# Electrode-Front-End-Digital.net
KiCad netlist of a schematic drawn in Altium Designer
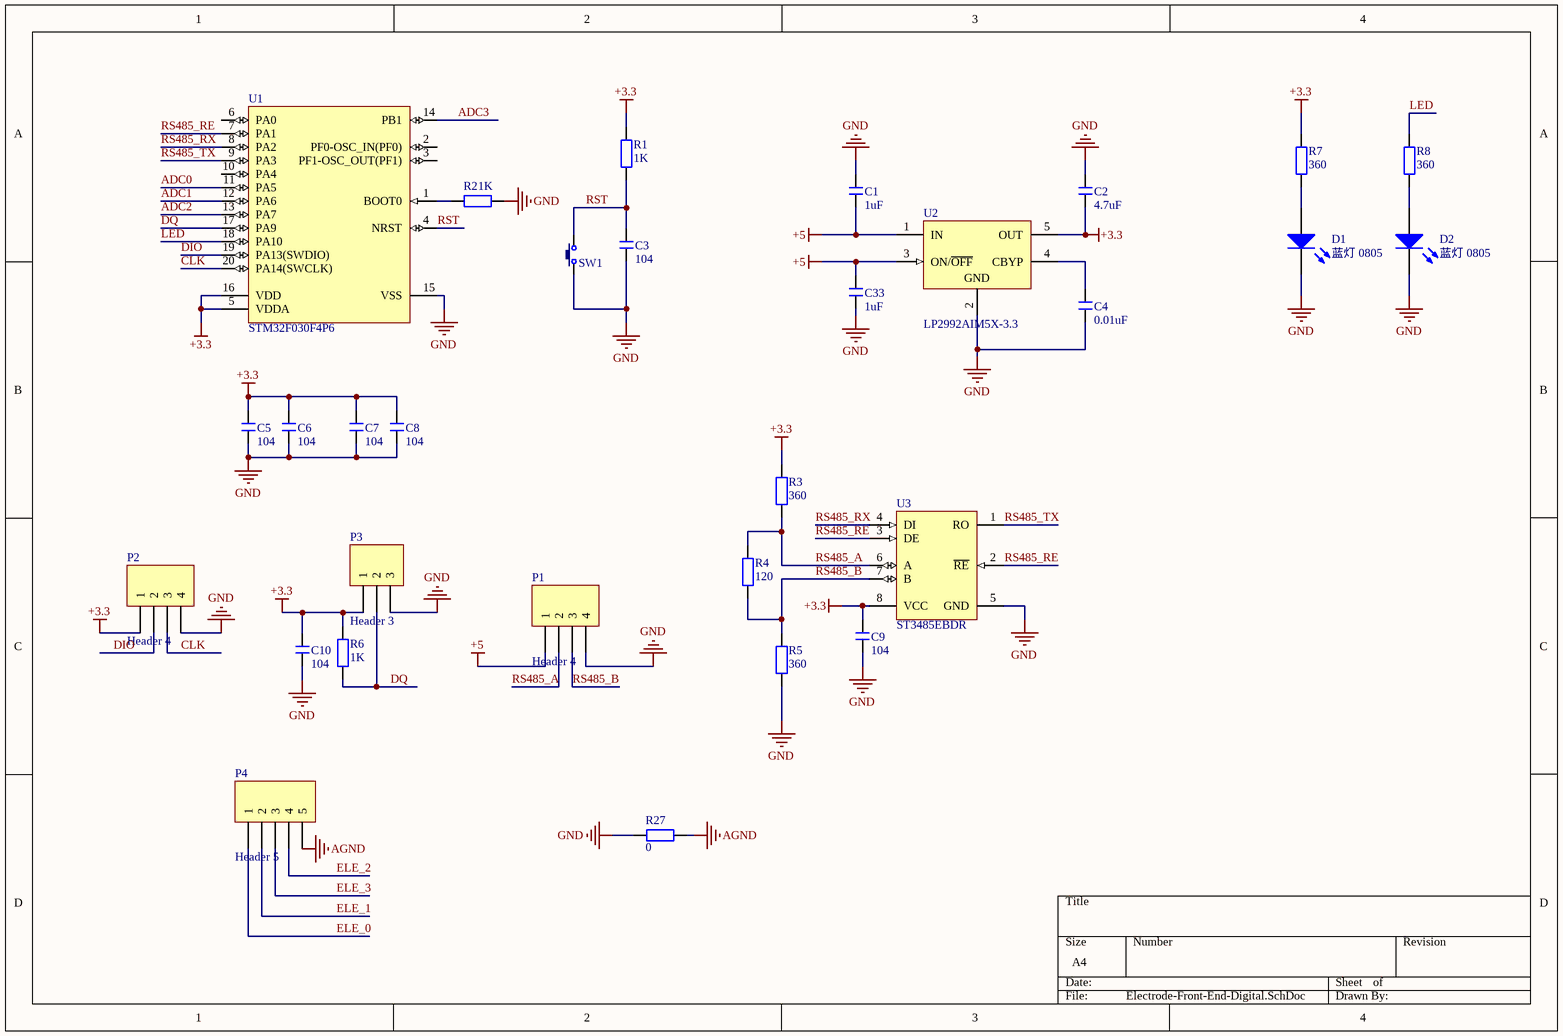
[diagram p0: Electrode-Front-End-Digital.SchDoc]

(export (version "E")
  (design (tool "Eeschema 10.0.6"))
  (components
    (comp (ref "C1")
      (value "1uF")
      (footprint "C 0603_L")
      (description "无极性贴片电容")
      (libsource (lib "电容-电阻-电感-电位器") (part "C"))
    )
    (comp (ref "C2")
      (value "4.7uF")
      (footprint "C 0603_L")
      (description "无极性贴片电容")
      (libsource (lib "电容-电阻-电感-电位器") (part "C"))
    )
    (comp (ref "C3")
      (value "104")
      (footprint "C 0603_L")
      (description "无极性贴片电容")
      (libsource (lib "电容-电阻-电感-电位器") (part "C"))
    )
    (comp (ref "C4")
      (value "0.01uF")
      (footprint "C 0603_L")
      (description "无极性贴片电容")
      (libsource (lib "电容-电阻-电感-电位器") (part "C"))
    )
    (comp (ref "C5")
      (value "104")
      (footprint "C 0603_L")
      (description "无极性贴片电容")
      (libsource (lib "电容-电阻-电感-电位器") (part "C"))
    )
    (comp (ref "C6")
      (value "104")
      (footprint "C 0603_L")
      (description "无极性贴片电容")
      (libsource (lib "电容-电阻-电感-电位器") (part "C"))
    )
    (comp (ref "C7")
      (value "104")
      (footprint "C 0603_L")
      (description "无极性贴片电容")
      (libsource (lib "电容-电阻-电感-电位器") (part "C"))
    )
    (comp (ref "C8")
      (value "104")
      (footprint "C 0603_L")
      (description "无极性贴片电容")
      (libsource (lib "电容-电阻-电感-电位器") (part "C"))
    )
    (comp (ref "C9")
      (value "104")
      (footprint "C 0603_L")
      (description "无极性贴片电容")
      (libsource (lib "电容-电阻-电感-电位器") (part "C"))
    )
    (comp (ref "C10")
      (value "104")
      (footprint "C 0603_L")
      (description "无极性贴片电容")
      (libsource (lib "电容-电阻-电感-电位器") (part "C"))
    )
    (comp (ref "C33")
      (value "1uF")
      (footprint "C 0603_L")
      (description "无极性贴片电容")
      (libsource (lib "电容-电阻-电感-电位器") (part "C"))
    )
    (comp (ref "D1")
      (value "蓝灯 0805")
      (footprint "0805_LED_S1")
      (description "发光二极管")
      (libsource (lib "JLC") (part "0805 蓝灯"))
    )
    (comp (ref "D2")
      (value "蓝灯 0805")
      (footprint "0805_LED_S1")
      (description "发光二极管")
      (libsource (lib "JLC") (part "0805 蓝灯"))
    )
    (comp (ref "P1")
      (value "Header 4")
      (footprint "HDR1X4")
      (description "Header, 4-Pin")
      (fields (field (name "PUBLISHER") "Altium Limited"))
      (libsource (lib "Miscellaneous Connectors") (part "Header 4"))
    )
    (comp (ref "P2")
      (value "Header 4")
      (footprint "HDR1X4")
      (description "Header, 4-Pin")
      (fields (field (name "PUBLISHER") "Altium Limited"))
      (libsource (lib "Miscellaneous Connectors") (part "Header 4"))
    )
    (comp (ref "P3")
      (value "Header 3")
      (footprint "HDR1X3")
      (description "Header, 3-Pin")
      (fields (field (name "PUBLISHER") "Altium Limited"))
      (libsource (lib "Miscellaneous Connectors") (part "Header 3"))
    )
    (comp (ref "P4")
      (value "Header 5")
      (footprint "HDR1X5")
      (description "Header, 5-Pin")
      (fields (field (name "PUBLISHER") "Altium Limited"))
      (libsource (lib "Miscellaneous Connectors") (part "Header 5"))
    )
    (comp (ref "R1")
      (value "1K")
      (footprint "R 0603_L")
      (description "贴片电阻")
      (libsource (lib "电容-电阻-电感-电位器") (part "R"))
    )
    (comp (ref "R2")
      (value "1K")
      (footprint "R 0603_L")
      (description "贴片电阻")
      (libsource (lib "电容-电阻-电感-电位器") (part "R"))
    )
    (comp (ref "R3")
      (value "360")
      (footprint "R 0603_L")
      (description "贴片电阻")
      (libsource (lib "电容-电阻-电感-电位器") (part "R"))
    )
    (comp (ref "R4")
      (value "120")
      (footprint "R 0603_L")
      (description "贴片电阻")
      (libsource (lib "电容-电阻-电感-电位器") (part "R"))
    )
    (comp (ref "R5")
      (value "360")
      (footprint "R 0603_L")
      (description "贴片电阻")
      (libsource (lib "电容-电阻-电感-电位器") (part "R"))
    )
    (comp (ref "R6")
      (value "1K")
      (footprint "R 0603_L")
      (description "贴片电阻")
      (libsource (lib "电容-电阻-电感-电位器") (part "R"))
    )
    (comp (ref "R7")
      (value "360")
      (footprint "R 0603_L")
      (description "贴片电阻")
      (libsource (lib "电容-电阻-电感-电位器") (part "R"))
    )
    (comp (ref "R8")
      (value "360")
      (footprint "R 0603_L")
      (description "贴片电阻")
      (libsource (lib "电容-电阻-电感-电位器") (part "R"))
    )
    (comp (ref "R27")
      (value "0")
      (footprint "R 0603_L")
      (description "贴片电阻")
      (libsource (lib "电容-电阻-电感-电位器") (part "R"))
    )
    (comp (ref "SW1")
      (value "3x6x5")
      (footprint "TSW SMD-3*6*2.5")
      (description "3x6轻触开关")
      (libsource (lib "按键-开关") (part "TSW 3x6"))
    )
    (comp (ref "U1")
      (value "STM32F030F4P6")
      (footprint "STM-TSSOP20_L")
      (libsource (lib "Altium Content Vault") (part "MC-ARM-STM32F030-IL20"))
    )
    (comp (ref "U2")
      (value "LP2992AIM5X-3.3")
      (footprint "MF05A_N")
      (description "Micropower 250 mA Low-Noise Ultra Low-Dropout Regulator, 5-pin SOT-23")
      (fields (field (name "MANUFACTURER") "National Semiconductor"))
      (libsource (lib "Altium Content Vault") (part "PM-REG-LP2985-SOT5"))
    )
    (comp (ref "U3")
      (value "ST3485EBDR")
      (footprint "STM-SO-8_C_L")
      (fields (field (name "MANUFACTURER") "STMicroelectronics"))
      (libsource (lib "Altium Content Vault") (part "STM-ST3485EBDR-SO-8"))
    )
  )
  (nets
    (net (code "1") (name "+3.3") (class "Default")
      (node (ref "C10") (pin "2") (pinfunction "2_2") (pintype "passive"))
      (node (ref "C2") (pin "1") (pinfunction "1_1") (pintype "passive"))
      (node (ref "C5") (pin "2") (pinfunction "2_2") (pintype "passive"))
      (node (ref "C6") (pin "2") (pinfunction "2_2") (pintype "passive"))
      (node (ref "C7") (pin "2") (pinfunction "2_2") (pintype "passive"))
      (node (ref "C8") (pin "2") (pinfunction "2_2") (pintype "passive"))
      (node (ref "C9") (pin "2") (pinfunction "2_2") (pintype "passive"))
      (node (ref "P2") (pin "1") (pinfunction "1_1") (pintype "passive"))
      (node (ref "P3") (pin "1") (pinfunction "1_1") (pintype "passive"))
      (node (ref "R1") (pin "2") (pinfunction "2_2") (pintype "passive"))
      (node (ref "R3") (pin "2") (pinfunction "2_2") (pintype "passive"))
      (node (ref "R6") (pin "2") (pinfunction "2_2") (pintype "passive"))
      (node (ref "R7") (pin "2") (pinfunction "2_2") (pintype "passive"))
      (node (ref "U1") (pin "16") (pinfunction "VDD_16") (pintype "power_in"))
      (node (ref "U1") (pin "5") (pinfunction "VDDA_5") (pintype "power_in"))
      (node (ref "U2") (pin "5") (pinfunction "OUT_5") (pintype "power_in"))
      (node (ref "U3") (pin "8") (pinfunction "VCC_8") (pintype "power_in"))
    )
    (net (code "2") (name "+5") (class "Default")
      (node (ref "C1") (pin "1") (pinfunction "1_1") (pintype "passive"))
      (node (ref "C33") (pin "2") (pinfunction "2_2") (pintype "passive"))
      (node (ref "P1") (pin "1") (pinfunction "1_1") (pintype "passive"))
      (node (ref "U2") (pin "1") (pinfunction "IN_1") (pintype "power_in"))
      (node (ref "U2") (pin "3") (pinfunction "ON/~{OFF}_3") (pintype "input"))
    )
    (net (code "3") (name "/ADC0") (class "Default")
      (node (ref "U1") (pin "11") (pinfunction "PA5_11") (pintype "bidirectional"))
    )
    (net (code "4") (name "/ADC1") (class "Default")
      (node (ref "U1") (pin "12") (pinfunction "PA6_12") (pintype "bidirectional"))
    )
    (net (code "5") (name "/ADC2") (class "Default")
      (node (ref "U1") (pin "13") (pinfunction "PA7_13") (pintype "bidirectional"))
    )
    (net (code "6") (name "/ADC3") (class "Default")
      (node (ref "U1") (pin "14") (pinfunction "PB1_14") (pintype "bidirectional"))
    )
    (net (code "7") (name "/CLK") (class "Default")
      (node (ref "P2") (pin "3") (pinfunction "3_3") (pintype "passive"))
      (node (ref "U1") (pin "20") (pinfunction "PA14(SWCLK)_20") (pintype "bidirectional"))
    )
    (net (code "8") (name "/DIO") (class "Default")
      (node (ref "P2") (pin "2") (pinfunction "2_2") (pintype "passive"))
      (node (ref "U1") (pin "19") (pinfunction "PA13(SWDIO)_19") (pintype "bidirectional"))
    )
    (net (code "9") (name "/DQ") (class "Default")
      (node (ref "P3") (pin "2") (pinfunction "2_2") (pintype "passive"))
      (node (ref "R6") (pin "1") (pinfunction "1_1") (pintype "passive"))
      (node (ref "U1") (pin "17") (pinfunction "PA9_17") (pintype "bidirectional"))
    )
    (net (code "10") (name "/ELE_0") (class "Default")
      (node (ref "P4") (pin "1") (pinfunction "1_1") (pintype "passive"))
    )
    (net (code "11") (name "/ELE_1") (class "Default")
      (node (ref "P4") (pin "2") (pinfunction "2_2") (pintype "passive"))
    )
    (net (code "12") (name "/ELE_2") (class "Default")
      (node (ref "P4") (pin "4") (pinfunction "4_4") (pintype "passive"))
    )
    (net (code "13") (name "/ELE_3") (class "Default")
      (node (ref "P4") (pin "3") (pinfunction "3_3") (pintype "passive"))
    )
    (net (code "14") (name "/LED") (class "Default")
      (node (ref "R8") (pin "2") (pinfunction "2_2") (pintype "passive"))
      (node (ref "U1") (pin "18") (pinfunction "PA10_18") (pintype "bidirectional"))
    )
    (net (code "15") (name "/RS485_A") (class "Default")
      (node (ref "P1") (pin "2") (pinfunction "2_2") (pintype "passive"))
      (node (ref "R3") (pin "1") (pinfunction "1_1") (pintype "passive"))
      (node (ref "R4") (pin "2") (pinfunction "2_2") (pintype "passive"))
      (node (ref "U3") (pin "6") (pinfunction "A_6") (pintype "bidirectional"))
    )
    (net (code "16") (name "/RS485_B") (class "Default")
      (node (ref "P1") (pin "3") (pinfunction "3_3") (pintype "passive"))
      (node (ref "R4") (pin "1") (pinfunction "1_1") (pintype "passive"))
      (node (ref "R5") (pin "2") (pinfunction "2_2") (pintype "passive"))
      (node (ref "U3") (pin "7") (pinfunction "B_7") (pintype "bidirectional"))
    )
    (net (code "17") (name "/RS485_RE") (class "Default")
      (node (ref "U1") (pin "7") (pinfunction "PA1_7") (pintype "bidirectional"))
      (node (ref "U3") (pin "2") (pinfunction "~{RE}_2") (pintype "input"))
      (node (ref "U3") (pin "3") (pinfunction "DE_3") (pintype "input"))
    )
    (net (code "18") (name "/RS485_RX") (class "Default")
      (node (ref "U1") (pin "8") (pinfunction "PA2_8") (pintype "bidirectional"))
      (node (ref "U3") (pin "4") (pinfunction "DI_4") (pintype "input"))
    )
    (net (code "19") (name "/RS485_TX") (class "Default")
      (node (ref "U1") (pin "9") (pinfunction "PA3_9") (pintype "bidirectional"))
      (node (ref "U3") (pin "1") (pinfunction "RO_1") (pintype "tri_state"))
    )
    (net (code "20") (name "/RST") (class "Default")
      (node (ref "C3") (pin "2") (pinfunction "2_2") (pintype "passive"))
      (node (ref "R1") (pin "1") (pinfunction "1_1") (pintype "passive"))
      (node (ref "SW1") (pin "2") (pinfunction "2_2") (pintype "passive"))
      (node (ref "U1") (pin "4") (pinfunction "NRST_4") (pintype "bidirectional"))
    )
    (net (code "21") (name "AGND") (class "Default")
      (node (ref "P4") (pin "5") (pinfunction "5_5") (pintype "passive"))
      (node (ref "R27") (pin "2") (pinfunction "2_2") (pintype "passive"))
    )
    (net (code "22") (name "GND") (class "Default")
      (node (ref "C1") (pin "2") (pinfunction "2_2") (pintype "passive"))
      (node (ref "C10") (pin "1") (pinfunction "1_1") (pintype "passive"))
      (node (ref "C2") (pin "2") (pinfunction "2_2") (pintype "passive"))
      (node (ref "C3") (pin "1") (pinfunction "1_1") (pintype "passive"))
      (node (ref "C33") (pin "1") (pinfunction "1_1") (pintype "passive"))
      (node (ref "C4") (pin "2") (pinfunction "2_2") (pintype "passive"))
      (node (ref "C5") (pin "1") (pinfunction "1_1") (pintype "passive"))
      (node (ref "C6") (pin "1") (pinfunction "1_1") (pintype "passive"))
      (node (ref "C7") (pin "1") (pinfunction "1_1") (pintype "passive"))
      (node (ref "C8") (pin "1") (pinfunction "1_1") (pintype "passive"))
      (node (ref "C9") (pin "1") (pinfunction "1_1") (pintype "passive"))
      (node (ref "D1") (pin "K") (pinfunction "K_K") (pintype "passive"))
      (node (ref "D2") (pin "K") (pinfunction "K_K") (pintype "passive"))
      (node (ref "P1") (pin "4") (pinfunction "4_4") (pintype "passive"))
      (node (ref "P2") (pin "4") (pinfunction "4_4") (pintype "passive"))
      (node (ref "P3") (pin "3") (pinfunction "3_3") (pintype "passive"))
      (node (ref "R2") (pin "2") (pinfunction "2_2") (pintype "passive"))
      (node (ref "R27") (pin "1") (pinfunction "1_1") (pintype "passive"))
      (node (ref "R5") (pin "1") (pinfunction "1_1") (pintype "passive"))
      (node (ref "SW1") (pin "1") (pinfunction "1_1") (pintype "passive"))
      (node (ref "U1") (pin "15") (pinfunction "VSS_15") (pintype "power_in"))
      (node (ref "U2") (pin "2") (pinfunction "GND_2") (pintype "power_in"))
      (node (ref "U3") (pin "5") (pinfunction "GND_5") (pintype "power_in"))
    )
    (net (code "23") (name "Net-(D1-PadA)") (class "Default")
      (node (ref "D1") (pin "A") (pinfunction "A_A") (pintype "passive"))
      (node (ref "R7") (pin "1") (pinfunction "1_1") (pintype "passive"))
    )
    (net (code "24") (name "Net-(D2-PadA)") (class "Default")
      (node (ref "D2") (pin "A") (pinfunction "A_A") (pintype "passive"))
      (node (ref "R8") (pin "1") (pinfunction "1_1") (pintype "passive"))
    )
    (net (code "25") (name "Net-(U1-BOOT0)") (class "Default")
      (node (ref "R2") (pin "1") (pinfunction "1_1") (pintype "passive"))
      (node (ref "U1") (pin "1") (pinfunction "BOOT0_1") (pintype "input"))
    )
    (net (code "26") (name "Net-(U2-CBYP)") (class "Default")
      (node (ref "C4") (pin "1") (pinfunction "1_1") (pintype "passive"))
      (node (ref "U2") (pin "4") (pinfunction "CBYP_4") (pintype "passive"))
    )
    (net (code "27") (name "unconnected-(U1-PA0-Pad6)") (class "Default")
      (node (ref "U1") (pin "6") (pinfunction "PA0_6") (pintype "bidirectional"))
    )
    (net (code "28") (name "unconnected-(U1-PA4-Pad10)") (class "Default")
      (node (ref "U1") (pin "10") (pinfunction "PA4_10") (pintype "bidirectional"))
    )
    (net (code "29") (name "unconnected-(U1-PF0-OSC_IN(PF0)-Pad2)") (class "Default")
      (node (ref "U1") (pin "2") (pinfunction "PF0-OSC_IN(PF0)_2") (pintype "bidirectional"))
    )
    (net (code "30") (name "unconnected-(U1-PF1-OSC_OUT(PF1)-Pad3)") (class "Default")
      (node (ref "U1") (pin "3") (pinfunction "PF1-OSC_OUT(PF1)_3") (pintype "bidirectional"))
    )
  )
)
